# untitled.net
KiCad netlist of a schematic drawn in EAGLE
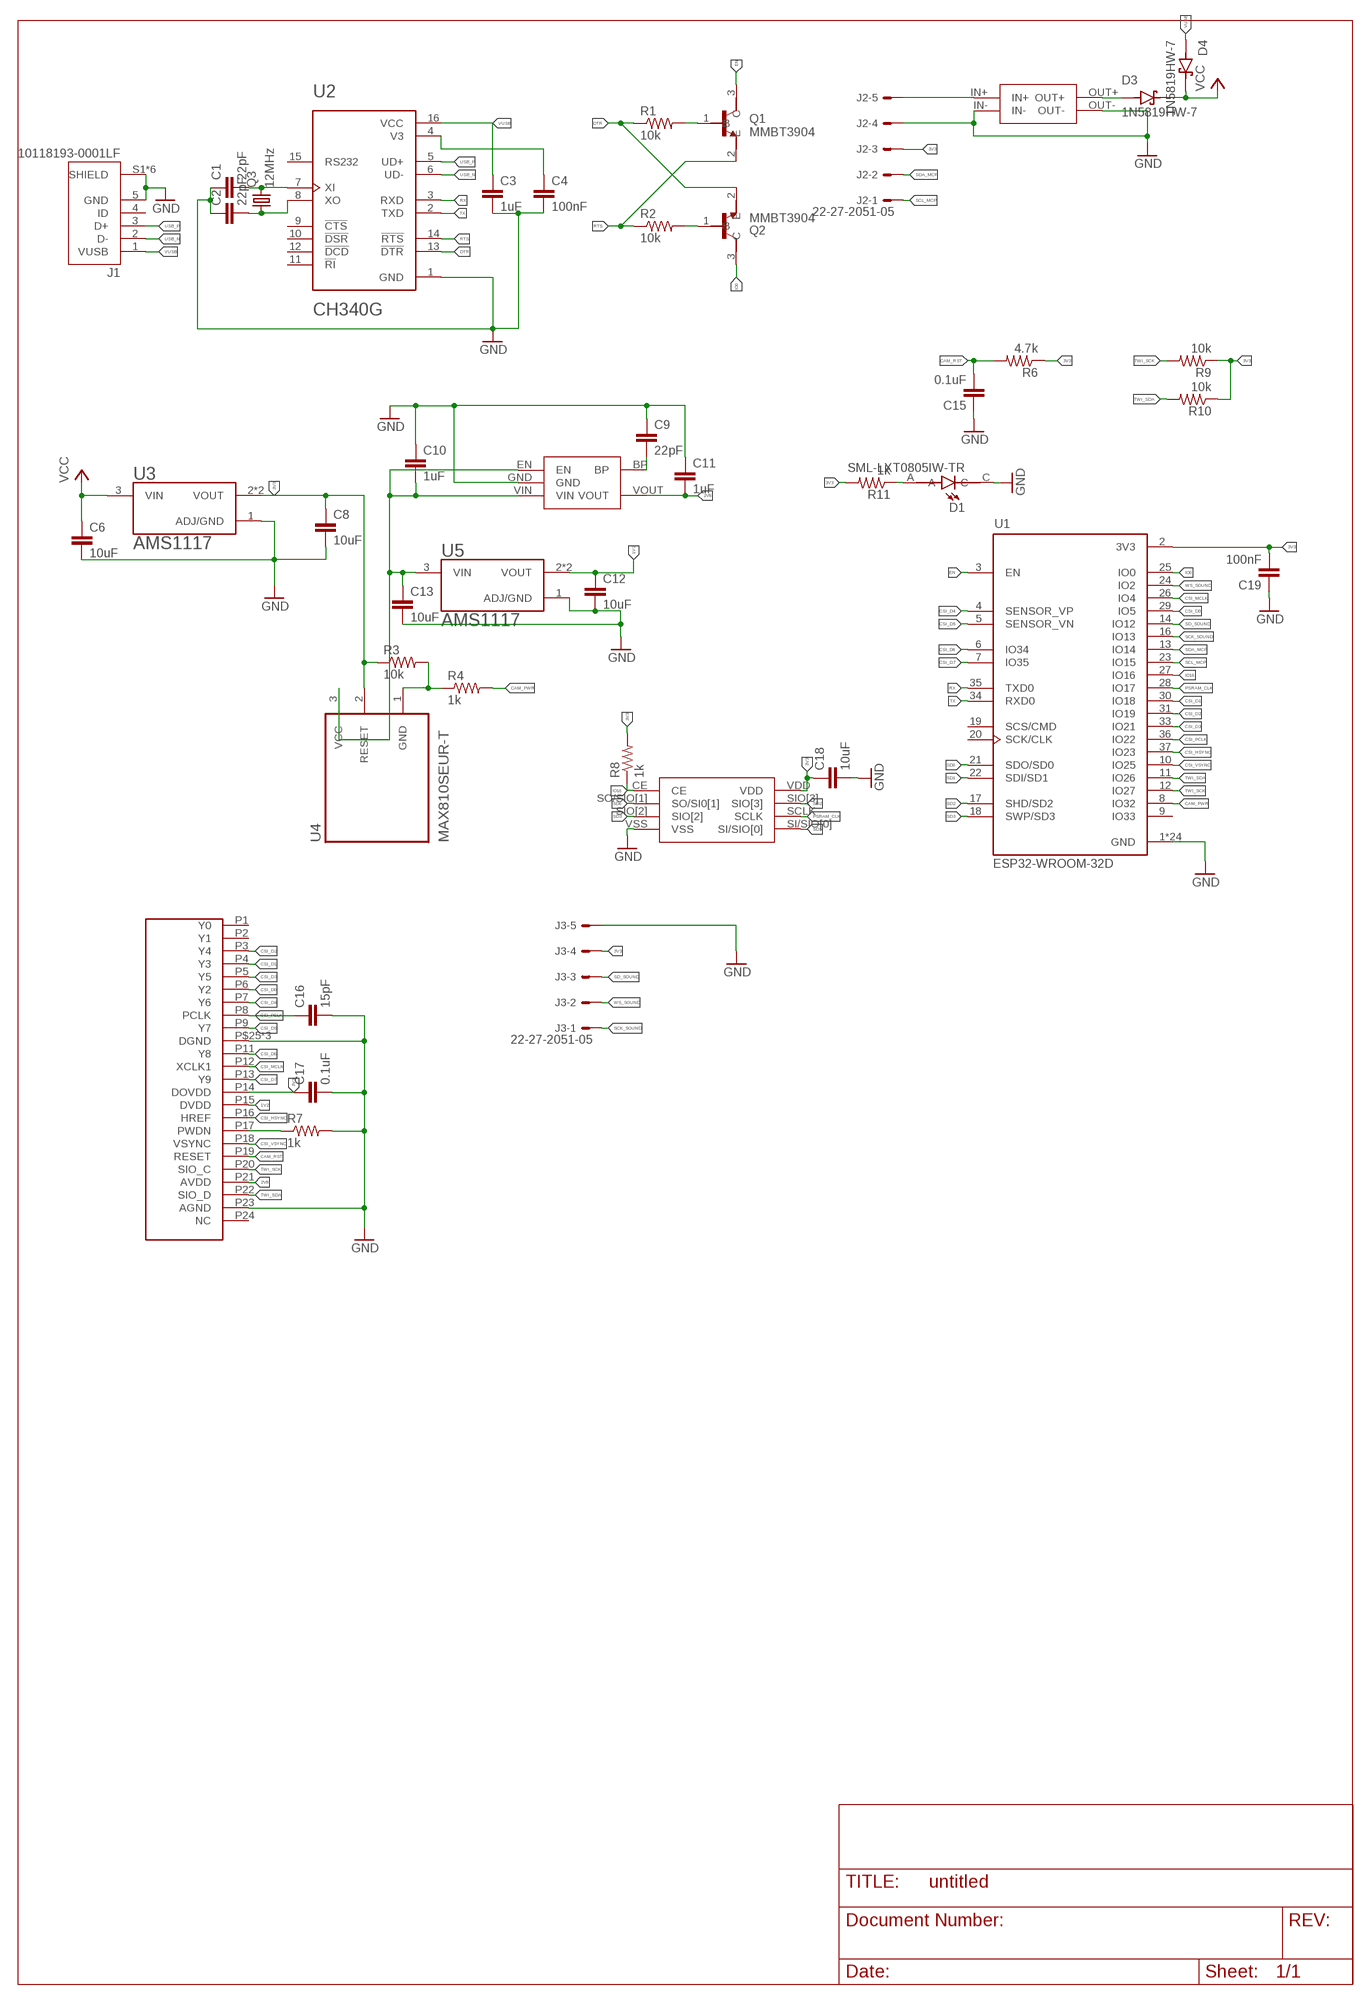
[diagram p0: schematic, sheet 1]

(export (version "E")
  (design (tool "Eeschema 10.0.6"))
  (components
    (comp (ref "APS6404L1")
      (value "APS6404L")
      (footprint "eagle-import:APS6404L")
      (libsource (lib "eagle-import") (part "APS6404L"))
    )
    (comp (ref "C1")
      (value "22pF")
      (footprint "eagle-import:C0805K")
      (libsource (lib "eagle-import") (part "C-EUC0805K"))
    )
    (comp (ref "C2")
      (value "22pF")
      (footprint "eagle-import:C0805K")
      (libsource (lib "eagle-import") (part "C-EUC0805K"))
    )
    (comp (ref "C3")
      (value "1uF")
      (footprint "eagle-import:C0805K")
      (libsource (lib "eagle-import") (part "C-EUC0805K"))
    )
    (comp (ref "C4")
      (value "100nF")
      (footprint "eagle-import:C0805K")
      (libsource (lib "eagle-import") (part "C-EUC0805K"))
    )
    (comp (ref "C6")
      (value "10uF")
      (footprint "eagle-import:C0805K")
      (libsource (lib "eagle-import") (part "C-EUC0805K"))
    )
    (comp (ref "C8")
      (value "10uF")
      (footprint "eagle-import:C0805K")
      (libsource (lib "eagle-import") (part "C-EUC0805K"))
    )
    (comp (ref "C9")
      (value "22pF")
      (footprint "eagle-import:C0805K")
      (libsource (lib "eagle-import") (part "C-EUC0805K"))
    )
    (comp (ref "C10")
      (value "1uF")
      (footprint "eagle-import:C0805K")
      (libsource (lib "eagle-import") (part "C-EUC0805K"))
    )
    (comp (ref "C11")
      (value "1uF")
      (footprint "eagle-import:C0805K")
      (libsource (lib "eagle-import") (part "C-EUC0805K"))
    )
    (comp (ref "C12")
      (value "10uF")
      (footprint "eagle-import:C0805K")
      (libsource (lib "eagle-import") (part "C-EUC0805K"))
    )
    (comp (ref "C13")
      (value "10uF")
      (footprint "eagle-import:C0805K")
      (libsource (lib "eagle-import") (part "C-EUC0805K"))
    )
    (comp (ref "C15")
      (value "0.1uF")
      (footprint "eagle-import:C0805K")
      (libsource (lib "eagle-import") (part "C-EUC0805K"))
    )
    (comp (ref "C16")
      (value "15pF")
      (footprint "eagle-import:C0805K")
      (libsource (lib "eagle-import") (part "C-EUC0805K"))
    )
    (comp (ref "C17")
      (value "0.1uF")
      (footprint "eagle-import:C0805K")
      (libsource (lib "eagle-import") (part "C-EUC0805K"))
    )
    (comp (ref "C18")
      (value "10uF")
      (footprint "eagle-import:C0805K")
      (libsource (lib "eagle-import") (part "C-EUC0805K"))
    )
    (comp (ref "C19")
      (value "100nF")
      (footprint "eagle-import:C0805K")
      (libsource (lib "eagle-import") (part "C-EUC0805K"))
    )
    (comp (ref "CAM1")
      (value "OV2640")
      (footprint "eagle-import:FPC-24")
      (fields (field (name "MF") "Omnivision Technologies"))
      (libsource (lib "eagle-import") (part "OV2640"))
    )
    (comp (ref "D1")
      (value "SML-LXT0805IW-TR")
      (footprint "eagle-import:LEDC2012X120N")
      (fields (field (name "MF") "Lumex Opto/Components"))
      (libsource (lib "eagle-import") (part "SML-LXT0805IW-TR"))
    )
    (comp (ref "D3")
      (value "1N5819HW-7")
      (footprint "eagle-import:SOD3715X145N")
      (fields (field (name "MF") "Diodes Inc."))
      (libsource (lib "eagle-import") (part "1N5819HW-7"))
    )
    (comp (ref "D4")
      (value "1N5819HW-7")
      (footprint "eagle-import:SOD3715X145N")
      (fields (field (name "MF") "Diodes Inc."))
      (libsource (lib "eagle-import") (part "1N5819HW-7"))
    )
    (comp (ref "J1")
      (value "10118193-0001LF")
      (footprint "eagle-import:FCI_10118193-0001LF")
      (fields (field (name "MF") "FCI"))
      (libsource (lib "eagle-import") (part "10118193-0001LF"))
    )
    (comp (ref "J2")
      (value "22-27-2051-05")
      (footprint "eagle-import:6410-05")
      (fields (field (name "MF") "MOLEX"))
      (libsource (lib "eagle-import") (part "22-?-0527-2051"))
    )
    (comp (ref "J3")
      (value "22-27-2051-05")
      (footprint "eagle-import:6410-05")
      (fields (field (name "MF") "MOLEX"))
      (libsource (lib "eagle-import") (part "22-?-0527-2051"))
    )
    (comp (ref "MINI1")
      (value "MINI560")
      (footprint "eagle-import:MINI560")
      (libsource (lib "eagle-import") (part "MINI560"))
    )
    (comp (ref "Q1")
      (value "MMBT3904")
      (footprint "eagle-import:SOT95P240X120-3N")
      (fields (field (name "MF") "ON Semiconductor"))
      (libsource (lib "eagle-import") (part "MMBT3904"))
    )
    (comp (ref "Q2")
      (value "MMBT3904")
      (footprint "eagle-import:SOT95P240X120-3N")
      (fields (field (name "MF") "ON Semiconductor"))
      (libsource (lib "eagle-import") (part "MMBT3904"))
    )
    (comp (ref "Q3")
      (value "12MHz")
      (footprint "eagle-import:SM49")
      (libsource (lib "eagle-import") (part "CRYSTALSM49"))
    )
    (comp (ref "R1")
      (value "10k")
      (footprint "eagle-import:M0805")
      (libsource (lib "eagle-import") (part "R-US_M0805"))
    )
    (comp (ref "R2")
      (value "10k")
      (footprint "eagle-import:M0805")
      (libsource (lib "eagle-import") (part "R-US_M0805"))
    )
    (comp (ref "R3")
      (value "10k")
      (footprint "eagle-import:M0805")
      (libsource (lib "eagle-import") (part "R-US_M0805"))
    )
    (comp (ref "R4")
      (value "1k")
      (footprint "eagle-import:M0805")
      (libsource (lib "eagle-import") (part "R-US_M0805"))
    )
    (comp (ref "R6")
      (value "4.7k")
      (footprint "eagle-import:M0805")
      (libsource (lib "eagle-import") (part "R-US_M0805"))
    )
    (comp (ref "R7")
      (value "1k")
      (footprint "eagle-import:M0805")
      (libsource (lib "eagle-import") (part "R-US_M0805"))
    )
    (comp (ref "R8")
      (value "1k")
      (footprint "eagle-import:M0805")
      (libsource (lib "eagle-import") (part "R-US_M0805"))
    )
    (comp (ref "R9")
      (value "10k")
      (footprint "eagle-import:M0805")
      (libsource (lib "eagle-import") (part "R-US_M0805"))
    )
    (comp (ref "R10")
      (value "10k")
      (footprint "eagle-import:M0805")
      (libsource (lib "eagle-import") (part "R-US_M0805"))
    )
    (comp (ref "R11")
      (value "1k")
      (footprint "eagle-import:M0805")
      (libsource (lib "eagle-import") (part "R-US_M0805"))
    )
    (comp (ref "RT9193-28GB1")
      (value "RT9193-28GB")
      (footprint "eagle-import:SOT94P279X129-5N")
      (libsource (lib "eagle-import") (part "RT9193-28GB"))
    )
    (comp (ref "U1")
      (value "ESP32-WROOM-32D")
      (footprint "eagle-import:MODULE_ESP32-WROOM-32D")
      (fields (field (name "MF") "Espressif Systems"))
      (libsource (lib "eagle-import") (part "ESP32-WROOM-32D"))
    )
    (comp (ref "U2")
      (value "CH340G")
      (footprint "eagle-import:SOIC127P600X180-16N")
      (fields (field (name "MF") "WCH") (field (name "MP") "Ch340G"))
      (libsource (lib "eagle-import") (part "CH340G"))
    )
    (comp (ref "U3")
      (value "AMS1117")
      (footprint "eagle-import:SOT229P700X180-4N")
      (fields (field (name "MF") "Advanced Monolithic Systems"))
      (libsource (lib "eagle-import") (part "AMS1117"))
    )
    (comp (ref "U4")
      (value "MAX810SEUR-T")
      (footprint "eagle-import:SOT95P237X112-3N")
      (fields (field (name "MF") "Analog Devices") (field (name "MP") "MAX810SEUR+T"))
      (libsource (lib "eagle-import") (part "MAX810SEUR-T"))
    )
    (comp (ref "U5")
      (value "AMS1117")
      (footprint "eagle-import:SOT229P700X180-4N")
      (fields (field (name "MF") "Advanced Monolithic Systems"))
      (libsource (lib "eagle-import") (part "AMS1117"))
    )
  )
  (nets
    (net (code "1") (name "1V2") (class "Default")
      (node (ref "C12") (pin "1") (pinfunction "1_1") (pintype "passive"))
      (node (ref "CAM1") (pin "P15") (pinfunction "DVDD_P15") (pintype "bidirectional"))
      (node (ref "U5") (pin "2") (pinfunction "VOUT_2") (pintype "output"))
      (node (ref "U5") (pin "4") (pinfunction "VOUT_4") (pintype "output"))
    )
    (net (code "2") (name "2V8") (class "Default")
      (node (ref "C11") (pin "2") (pinfunction "2_2") (pintype "passive"))
      (node (ref "CAM1") (pin "P21") (pinfunction "AVDD_P21") (pintype "bidirectional"))
      (node (ref "RT9193-28GB1") (pin "VOUT") (pinfunction "VOUT_VOUT") (pintype "bidirectional"))
    )
    (net (code "3") (name "3V3") (class "Default")
      (node (ref "APS6404L1") (pin "VDD") (pinfunction "VDD_VDD") (pintype "bidirectional"))
      (node (ref "C17") (pin "1") (pinfunction "1_1") (pintype "passive"))
      (node (ref "C18") (pin "1") (pinfunction "1_1") (pintype "passive"))
      (node (ref "C19") (pin "2") (pinfunction "2_2") (pintype "passive"))
      (node (ref "C8") (pin "1") (pinfunction "1_1") (pintype "passive"))
      (node (ref "CAM1") (pin "P14") (pinfunction "DOVDD_P14") (pintype "bidirectional"))
      (node (ref "J2") (pin "3") (pinfunction "S_3") (pintype "passive"))
      (node (ref "J3") (pin "4") (pinfunction "S_4") (pintype "passive"))
      (node (ref "R10") (pin "1") (pinfunction "1_1") (pintype "passive"))
      (node (ref "R11") (pin "2") (pinfunction "2_2") (pintype "passive"))
      (node (ref "R3") (pin "1") (pinfunction "1_1") (pintype "passive"))
      (node (ref "R6") (pin "1") (pinfunction "1_1") (pintype "passive"))
      (node (ref "R8") (pin "2") (pinfunction "2_2") (pintype "passive"))
      (node (ref "R9") (pin "1") (pinfunction "1_1") (pintype "passive"))
      (node (ref "U1") (pin "2") (pinfunction "3V3_2") (pintype "power_in"))
      (node (ref "U3") (pin "2") (pinfunction "VOUT_2") (pintype "output"))
      (node (ref "U3") (pin "4") (pinfunction "VOUT_4") (pintype "output"))
      (node (ref "U4") (pin "2") (pinfunction "RESET_2") (pintype "output"))
    )
    (net (code "4") (name "CAM_PWR") (class "Default")
      (node (ref "R4") (pin "2") (pinfunction "2_2") (pintype "passive"))
      (node (ref "U1") (pin "8") (pinfunction "IO32_8") (pintype "bidirectional"))
    )
    (net (code "5") (name "CAM_RST") (class "Default")
      (node (ref "C15") (pin "2") (pinfunction "2_2") (pintype "passive"))
      (node (ref "CAM1") (pin "P19") (pinfunction "RESET_P19") (pintype "bidirectional"))
      (node (ref "R6") (pin "2") (pinfunction "2_2") (pintype "passive"))
    )
    (net (code "6") (name "CSI_D0") (class "Default")
      (node (ref "CAM1") (pin "P6") (pinfunction "Y2_P6") (pintype "bidirectional"))
      (node (ref "U1") (pin "29") (pinfunction "IO5_29") (pintype "bidirectional"))
    )
    (net (code "7") (name "CSI_D1") (class "Default")
      (node (ref "CAM1") (pin "P4") (pinfunction "Y3_P4") (pintype "bidirectional"))
      (node (ref "U1") (pin "30") (pinfunction "IO18_30") (pintype "bidirectional"))
    )
    (net (code "8") (name "CSI_D2") (class "Default")
      (node (ref "CAM1") (pin "P3") (pinfunction "Y4_P3") (pintype "bidirectional"))
      (node (ref "U1") (pin "31") (pinfunction "IO19_31") (pintype "bidirectional"))
    )
    (net (code "9") (name "CSI_D3") (class "Default")
      (node (ref "CAM1") (pin "P5") (pinfunction "Y5_P5") (pintype "bidirectional"))
      (node (ref "U1") (pin "33") (pinfunction "IO21_33") (pintype "bidirectional"))
    )
    (net (code "10") (name "CSI_D4") (class "Default")
      (node (ref "CAM1") (pin "P7") (pinfunction "Y6_P7") (pintype "bidirectional"))
      (node (ref "U1") (pin "4") (pinfunction "SENSOR_VP_4") (pintype "input"))
    )
    (net (code "11") (name "CSI_D5") (class "Default")
      (node (ref "CAM1") (pin "P9") (pinfunction "Y7_P9") (pintype "bidirectional"))
      (node (ref "U1") (pin "5") (pinfunction "SENSOR_VN_5") (pintype "input"))
    )
    (net (code "12") (name "CSI_D6") (class "Default")
      (node (ref "CAM1") (pin "P11") (pinfunction "Y8_P11") (pintype "bidirectional"))
      (node (ref "U1") (pin "6") (pinfunction "IO34_6") (pintype "input"))
    )
    (net (code "13") (name "CSI_D7") (class "Default")
      (node (ref "CAM1") (pin "P13") (pinfunction "Y9_P13") (pintype "bidirectional"))
      (node (ref "U1") (pin "7") (pinfunction "IO35_7") (pintype "input"))
    )
    (net (code "14") (name "CSI_HSYNC") (class "Default")
      (node (ref "CAM1") (pin "P16") (pinfunction "HREF_P16") (pintype "bidirectional"))
      (node (ref "U1") (pin "37") (pinfunction "IO23_37") (pintype "bidirectional"))
    )
    (net (code "15") (name "CSI_MCLK") (class "Default")
      (node (ref "CAM1") (pin "P12") (pinfunction "XCLK1_P12") (pintype "bidirectional"))
      (node (ref "U1") (pin "26") (pinfunction "IO4_26") (pintype "bidirectional"))
    )
    (net (code "16") (name "CSI_PCLK") (class "Default")
      (node (ref "C16") (pin "1") (pinfunction "1_1") (pintype "passive"))
      (node (ref "CAM1") (pin "P8") (pinfunction "PCLK_P8") (pintype "bidirectional"))
      (node (ref "U1") (pin "36") (pinfunction "IO22_36") (pintype "bidirectional"))
    )
    (net (code "17") (name "CSI_VSYNC") (class "Default")
      (node (ref "CAM1") (pin "P18") (pinfunction "VSYNC_P18") (pintype "bidirectional"))
      (node (ref "U1") (pin "10") (pinfunction "IO25_10") (pintype "bidirectional"))
    )
    (net (code "18") (name "DTR") (class "Default")
      (node (ref "Q2") (pin "2") (pinfunction "E_2") (pintype "passive"))
      (node (ref "R1") (pin "1") (pinfunction "1_1") (pintype "passive"))
      (node (ref "U2") (pin "13") (pinfunction "~{DTR}_13") (pintype "output"))
    )
    (net (code "19") (name "EN") (class "Default")
      (node (ref "Q1") (pin "3") (pinfunction "C_3") (pintype "passive"))
      (node (ref "U1") (pin "3") (pinfunction "EN_3") (pintype "input"))
    )
    (net (code "20") (name "GND") (class "Default")
      (node (ref "APS6404L1") (pin "VSS") (pinfunction "VSS_VSS") (pintype "bidirectional"))
      (node (ref "C1") (pin "1") (pinfunction "1_1") (pintype "passive"))
      (node (ref "C10") (pin "1") (pinfunction "1_1") (pintype "passive"))
      (node (ref "C11") (pin "1") (pinfunction "1_1") (pintype "passive"))
      (node (ref "C12") (pin "2") (pinfunction "2_2") (pintype "passive"))
      (node (ref "C13") (pin "2") (pinfunction "2_2") (pintype "passive"))
      (node (ref "C15") (pin "1") (pinfunction "1_1") (pintype "passive"))
      (node (ref "C16") (pin "2") (pinfunction "2_2") (pintype "passive"))
      (node (ref "C17") (pin "2") (pinfunction "2_2") (pintype "passive"))
      (node (ref "C18") (pin "2") (pinfunction "2_2") (pintype "passive"))
      (node (ref "C19") (pin "1") (pinfunction "1_1") (pintype "passive"))
      (node (ref "C2") (pin "1") (pinfunction "1_1") (pintype "passive"))
      (node (ref "C3") (pin "2") (pinfunction "2_2") (pintype "passive"))
      (node (ref "C4") (pin "2") (pinfunction "2_2") (pintype "passive"))
      (node (ref "C6") (pin "2") (pinfunction "2_2") (pintype "passive"))
      (node (ref "C8") (pin "2") (pinfunction "2_2") (pintype "passive"))
      (node (ref "C9") (pin "1") (pinfunction "1_1") (pintype "passive"))
      (node (ref "CAM1") (pin "P$25") (pinfunction "DGND_P$25") (pintype "bidirectional"))
      (node (ref "CAM1") (pin "P$26") (pinfunction "DGND_P$26") (pintype "bidirectional"))
      (node (ref "CAM1") (pin "P10") (pinfunction "DGND_P10") (pintype "bidirectional"))
      (node (ref "CAM1") (pin "P23") (pinfunction "AGND_P23") (pintype "bidirectional"))
      (node (ref "D1") (pin "C") (pinfunction "C_C") (pintype "passive"))
      (node (ref "J1") (pin "5") (pinfunction "GND_5") (pintype "passive"))
      (node (ref "J1") (pin "S1") (pinfunction "SHIELD_S1") (pintype "passive"))
      (node (ref "J1") (pin "S2") (pinfunction "SHIELD_S2") (pintype "passive"))
      (node (ref "J1") (pin "S3") (pinfunction "SHIELD_S3") (pintype "passive"))
      (node (ref "J1") (pin "S4") (pinfunction "SHIELD_S4") (pintype "passive"))
      (node (ref "J1") (pin "S5") (pinfunction "SHIELD_S5") (pintype "passive"))
      (node (ref "J1") (pin "S6") (pinfunction "SHIELD_S6") (pintype "passive"))
      (node (ref "J2") (pin "4") (pinfunction "S_4") (pintype "passive"))
      (node (ref "J3") (pin "5") (pinfunction "S_5") (pintype "passive"))
      (node (ref "MINI1") (pin "IN-") (pinfunction "IN-_IN-") (pintype "bidirectional"))
      (node (ref "MINI1") (pin "OUT-") (pinfunction "OUT-_OUT-") (pintype "bidirectional"))
      (node (ref "R7") (pin "2") (pinfunction "2_2") (pintype "passive"))
      (node (ref "RT9193-28GB1") (pin "GND") (pinfunction "GND_GND") (pintype "bidirectional"))
      (node (ref "U1") (pin "1") (pinfunction "GND_1") (pintype "power_in"))
      (node (ref "U1") (pin "15") (pinfunction "GND_15") (pintype "power_in"))
      (node (ref "U1") (pin "38") (pinfunction "GND_38") (pintype "power_in"))
      (node (ref "U1") (pin "39_1") (pinfunction "GND_39_1") (pintype "power_in"))
      (node (ref "U1") (pin "39_10") (pinfunction "GND_39_10") (pintype "power_in"))
      (node (ref "U1") (pin "39_11") (pinfunction "GND_39_11") (pintype "power_in"))
      (node (ref "U1") (pin "39_12") (pinfunction "GND_39_12") (pintype "power_in"))
      (node (ref "U1") (pin "39_13") (pinfunction "GND_39_13") (pintype "power_in"))
      (node (ref "U1") (pin "39_14") (pinfunction "GND_39_14") (pintype "power_in"))
      (node (ref "U1") (pin "39_15") (pinfunction "GND_39_15") (pintype "power_in"))
      (node (ref "U1") (pin "39_16") (pinfunction "GND_39_16") (pintype "power_in"))
      (node (ref "U1") (pin "39_17") (pinfunction "GND_39_17") (pintype "power_in"))
      (node (ref "U1") (pin "39_18") (pinfunction "GND_39_18") (pintype "power_in"))
      (node (ref "U1") (pin "39_19") (pinfunction "GND_39_19") (pintype "power_in"))
      (node (ref "U1") (pin "39_2") (pinfunction "GND_39_2") (pintype "power_in"))
      (node (ref "U1") (pin "39_20") (pinfunction "GND_39_20") (pintype "power_in"))
      (node (ref "U1") (pin "39_21") (pinfunction "GND_39_21") (pintype "power_in"))
      (node (ref "U1") (pin "39_3") (pinfunction "GND_39_3") (pintype "power_in"))
      (node (ref "U1") (pin "39_4") (pinfunction "GND_39_4") (pintype "power_in"))
      (node (ref "U1") (pin "39_5") (pinfunction "GND_39_5") (pintype "power_in"))
      (node (ref "U1") (pin "39_6") (pinfunction "GND_39_6") (pintype "power_in"))
      (node (ref "U1") (pin "39_7") (pinfunction "GND_39_7") (pintype "power_in"))
      (node (ref "U1") (pin "39_8") (pinfunction "GND_39_8") (pintype "power_in"))
      (node (ref "U1") (pin "39_9") (pinfunction "GND_39_9") (pintype "power_in"))
      (node (ref "U2") (pin "1") (pinfunction "GND_1") (pintype "power_in"))
      (node (ref "U3") (pin "1") (pinfunction "ADJ/GND_1") (pintype "power_in"))
      (node (ref "U5") (pin "1") (pinfunction "ADJ/GND_1") (pintype "power_in"))
    )
    (net (code "21") (name "IO0") (class "Default")
      (node (ref "Q2") (pin "3") (pinfunction "C_3") (pintype "passive"))
      (node (ref "U1") (pin "25") (pinfunction "IO0_25") (pintype "bidirectional"))
    )
    (net (code "22") (name "IO16") (class "Default")
      (node (ref "APS6404L1") (pin "CE") (pinfunction "CE_CE") (pintype "bidirectional"))
      (node (ref "R8") (pin "1") (pinfunction "1_1") (pintype "passive"))
      (node (ref "U1") (pin "27") (pinfunction "IO16_27") (pintype "bidirectional"))
    )
    (net (code "23") (name "Net-(C9-Pad2)") (class "Default")
      (node (ref "C9") (pin "2") (pinfunction "2_2") (pintype "passive"))
      (node (ref "RT9193-28GB1") (pin "BP") (pinfunction "BP_BP") (pintype "bidirectional"))
    )
    (net (code "24") (name "Net-(CAM1-PWDN)") (class "Default")
      (node (ref "CAM1") (pin "P17") (pinfunction "PWDN_P17") (pintype "bidirectional"))
      (node (ref "R7") (pin "1") (pinfunction "1_1") (pintype "passive"))
    )
    (net (code "25") (name "Net-(D1-PadA)") (class "Default")
      (node (ref "D1") (pin "A") (pinfunction "A_A") (pintype "passive"))
      (node (ref "R11") (pin "1") (pinfunction "1_1") (pintype "passive"))
    )
    (net (code "26") (name "Net-(D3-PadA)") (class "Default")
      (node (ref "D3") (pin "A") (pinfunction "A_A") (pintype "passive"))
      (node (ref "MINI1") (pin "OUT+") (pinfunction "OUT+_OUT+") (pintype "bidirectional"))
    )
    (net (code "27") (name "Net-(J2E-S)") (class "Default")
      (node (ref "J2") (pin "5") (pinfunction "S_5") (pintype "passive"))
      (node (ref "MINI1") (pin "IN+") (pinfunction "IN+_IN+") (pintype "bidirectional"))
    )
    (net (code "28") (name "Net-(Q1-B)") (class "Default")
      (node (ref "Q1") (pin "1") (pinfunction "B_1") (pintype "passive"))
      (node (ref "R1") (pin "2") (pinfunction "2_2") (pintype "passive"))
    )
    (net (code "29") (name "Net-(Q2-B)") (class "Default")
      (node (ref "Q2") (pin "1") (pinfunction "B_1") (pintype "passive"))
      (node (ref "R2") (pin "2") (pinfunction "2_2") (pintype "passive"))
    )
    (net (code "30") (name "Net-(U2-V3)") (class "Default")
      (node (ref "C4") (pin "1") (pinfunction "1_1") (pintype "passive"))
      (node (ref "U2") (pin "4") (pinfunction "V3_4") (pintype "power_in"))
    )
    (net (code "31") (name "Net-(U2-XI)") (class "Default")
      (node (ref "C1") (pin "2") (pinfunction "2_2") (pintype "passive"))
      (node (ref "Q3") (pin "2") (pinfunction "2_2") (pintype "passive"))
      (node (ref "U2") (pin "7") (pinfunction "XI_7") (pintype "input"))
    )
    (net (code "32") (name "Net-(U2-XO)") (class "Default")
      (node (ref "C2") (pin "2") (pinfunction "2_2") (pintype "passive"))
      (node (ref "Q3") (pin "1") (pinfunction "1_1") (pintype "passive"))
      (node (ref "U2") (pin "8") (pinfunction "XO_8") (pintype "output"))
    )
    (net (code "33") (name "Net-(U4-GND)") (class "Default")
      (node (ref "R3") (pin "2") (pinfunction "2_2") (pintype "passive"))
      (node (ref "R4") (pin "1") (pinfunction "1_1") (pintype "passive"))
      (node (ref "U4") (pin "1") (pinfunction "GND_1") (pintype "power_in"))
    )
    (net (code "34") (name "Net-(U4-VCC)") (class "Default")
      (node (ref "C10") (pin "2") (pinfunction "2_2") (pintype "passive"))
      (node (ref "C13") (pin "1") (pinfunction "1_1") (pintype "passive"))
      (node (ref "RT9193-28GB1") (pin "EN") (pinfunction "EN_EN") (pintype "bidirectional"))
      (node (ref "RT9193-28GB1") (pin "VIN") (pinfunction "VIN_VIN") (pintype "bidirectional"))
      (node (ref "U4") (pin "3") (pinfunction "VCC_3") (pintype "power_in"))
      (node (ref "U5") (pin "3") (pinfunction "VIN_3") (pintype "input"))
    )
    (net (code "35") (name "PSRAM_CLK") (class "Default")
      (node (ref "APS6404L1") (pin "SCLK") (pinfunction "SCLK_SCLK") (pintype "bidirectional"))
      (node (ref "U1") (pin "28") (pinfunction "IO17_28") (pintype "bidirectional"))
    )
    (net (code "36") (name "RTS") (class "Default")
      (node (ref "Q1") (pin "2") (pinfunction "E_2") (pintype "passive"))
      (node (ref "R2") (pin "1") (pinfunction "1_1") (pintype "passive"))
      (node (ref "U2") (pin "14") (pinfunction "~{RTS}_14") (pintype "output"))
    )
    (net (code "37") (name "RX") (class "Default")
      (node (ref "U1") (pin "35") (pinfunction "TXD0_35") (pintype "bidirectional"))
      (node (ref "U2") (pin "3") (pinfunction "RXD_3") (pintype "input"))
    )
    (net (code "38") (name "SCK_SOUND") (class "Default")
      (node (ref "J3") (pin "1") (pinfunction "S_1") (pintype "passive"))
      (node (ref "U1") (pin "16") (pinfunction "IO13_16") (pintype "bidirectional"))
    )
    (net (code "39") (name "SCL_MCP") (class "Default")
      (node (ref "J2") (pin "1") (pinfunction "S_1") (pintype "passive"))
      (node (ref "U1") (pin "23") (pinfunction "IO15_23") (pintype "bidirectional"))
    )
    (net (code "40") (name "SD0") (class "Default")
      (node (ref "APS6404L1") (pin "SO/SIO[1]") (pinfunction "SO/SI0[1]_SO/SIO[1]") (pintype "bidirectional"))
      (node (ref "U1") (pin "21") (pinfunction "SDO/SD0_21") (pintype "bidirectional"))
    )
    (net (code "41") (name "SD1") (class "Default")
      (node (ref "APS6404L1") (pin "SI/SIO[0]") (pinfunction "SI/SIO[0]_SI/SIO[0]") (pintype "bidirectional"))
      (node (ref "U1") (pin "22") (pinfunction "SDI/SD1_22") (pintype "bidirectional"))
    )
    (net (code "42") (name "SD2") (class "Default")
      (node (ref "APS6404L1") (pin "SIO[3]") (pinfunction "SIO[3]_SIO[3]") (pintype "bidirectional"))
      (node (ref "U1") (pin "17") (pinfunction "SHD/SD2_17") (pintype "bidirectional"))
    )
    (net (code "43") (name "SD3") (class "Default")
      (node (ref "APS6404L1") (pin "SIO[2]") (pinfunction "SIO[2]_SIO[2]") (pintype "bidirectional"))
      (node (ref "U1") (pin "18") (pinfunction "SWP/SD3_18") (pintype "bidirectional"))
    )
    (net (code "44") (name "SDA_MCP") (class "Default")
      (node (ref "J2") (pin "2") (pinfunction "S_2") (pintype "passive"))
      (node (ref "U1") (pin "13") (pinfunction "IO14_13") (pintype "bidirectional"))
    )
    (net (code "45") (name "SD_SOUND") (class "Default")
      (node (ref "J3") (pin "3") (pinfunction "S_3") (pintype "passive"))
      (node (ref "U1") (pin "14") (pinfunction "IO12_14") (pintype "bidirectional"))
    )
    (net (code "46") (name "TWI_SCK") (class "Default")
      (node (ref "CAM1") (pin "P20") (pinfunction "SIO_C_P20") (pintype "bidirectional"))
      (node (ref "R9") (pin "2") (pinfunction "2_2") (pintype "passive"))
      (node (ref "U1") (pin "12") (pinfunction "IO27_12") (pintype "bidirectional"))
    )
    (net (code "47") (name "TWI_SDA") (class "Default")
      (node (ref "CAM1") (pin "P22") (pinfunction "SIO_D_P22") (pintype "bidirectional"))
      (node (ref "R10") (pin "2") (pinfunction "2_2") (pintype "passive"))
      (node (ref "U1") (pin "11") (pinfunction "IO26_11") (pintype "bidirectional"))
    )
    (net (code "48") (name "TX") (class "Default")
      (node (ref "U1") (pin "34") (pinfunction "RXD0_34") (pintype "bidirectional"))
      (node (ref "U2") (pin "2") (pinfunction "TXD_2") (pintype "output"))
    )
    (net (code "49") (name "USB_N") (class "Default")
      (node (ref "J1") (pin "2") (pinfunction "D-_2") (pintype "passive"))
      (node (ref "U2") (pin "6") (pinfunction "UD-_6") (pintype "bidirectional"))
    )
    (net (code "50") (name "USB_P") (class "Default")
      (node (ref "J1") (pin "3") (pinfunction "D+_3") (pintype "passive"))
      (node (ref "U2") (pin "5") (pinfunction "UD+_5") (pintype "bidirectional"))
    )
    (net (code "51") (name "VCC") (class "Default")
      (node (ref "C6") (pin "1") (pinfunction "1_1") (pintype "passive"))
      (node (ref "D3") (pin "C") (pinfunction "K_C") (pintype "passive"))
      (node (ref "D4") (pin "C") (pinfunction "K_C") (pintype "passive"))
      (node (ref "U3") (pin "3") (pinfunction "VIN_3") (pintype "input"))
    )
    (net (code "52") (name "VUSB") (class "Default")
      (node (ref "C3") (pin "1") (pinfunction "1_1") (pintype "passive"))
      (node (ref "D4") (pin "A") (pinfunction "A_A") (pintype "passive"))
      (node (ref "J1") (pin "1") (pinfunction "VUSB_1") (pintype "passive"))
      (node (ref "U2") (pin "16") (pinfunction "VCC_16") (pintype "power_in"))
    )
    (net (code "53") (name "WS_SOUND") (class "Default")
      (node (ref "J3") (pin "2") (pinfunction "S_2") (pintype "passive"))
      (node (ref "U1") (pin "24") (pinfunction "IO2_24") (pintype "bidirectional"))
    )
    (net (code "54") (name "unconnected-(CAM1-NC-PadP24)") (class "Default")
      (node (ref "CAM1") (pin "P24") (pinfunction "NC_P24") (pintype "bidirectional"))
    )
    (net (code "55") (name "unconnected-(CAM1-Y0-PadP1)") (class "Default")
      (node (ref "CAM1") (pin "P1") (pinfunction "Y0_P1") (pintype "bidirectional"))
    )
    (net (code "56") (name "unconnected-(CAM1-Y1-PadP2)") (class "Default")
      (node (ref "CAM1") (pin "P2") (pinfunction "Y1_P2") (pintype "bidirectional"))
    )
    (net (code "57") (name "unconnected-(J1-ID-Pad4)") (class "Default")
      (node (ref "J1") (pin "4") (pinfunction "ID_4") (pintype "passive"))
    )
    (net (code "58") (name "unconnected-(U1-IO33-Pad9)") (class "Default")
      (node (ref "U1") (pin "9") (pinfunction "IO33_9") (pintype "bidirectional"))
    )
    (net (code "59") (name "unconnected-(U1-SCK{slash}CLK-Pad20)") (class "Default")
      (node (ref "U1") (pin "20") (pinfunction "SCK/CLK_20") (pintype "bidirectional"))
    )
    (net (code "60") (name "unconnected-(U1-SCS{slash}CMD-Pad19)") (class "Default")
      (node (ref "U1") (pin "19") (pinfunction "SCS/CMD_19") (pintype "bidirectional"))
    )
    (net (code "61") (name "unconnected-(U2-RS232-Pad15)") (class "Default")
      (node (ref "U2") (pin "15") (pinfunction "RS232_15") (pintype "input"))
    )
    (net (code "62") (name "unconnected-(U2-~{CTS}-Pad9)") (class "Default")
      (node (ref "U2") (pin "9") (pinfunction "~{CTS}_9") (pintype "input"))
    )
    (net (code "63") (name "unconnected-(U2-~{DCD}-Pad12)") (class "Default")
      (node (ref "U2") (pin "12") (pinfunction "~{DCD}_12") (pintype "input"))
    )
    (net (code "64") (name "unconnected-(U2-~{DSR}-Pad10)") (class "Default")
      (node (ref "U2") (pin "10") (pinfunction "~{DSR}_10") (pintype "input"))
    )
    (net (code "65") (name "unconnected-(U2-~{RI}-Pad11)") (class "Default")
      (node (ref "U2") (pin "11") (pinfunction "~{RI}_11") (pintype "input"))
    )
  )
)
